# main1.net
KiCad netlist of a schematic drawn in EAGLE
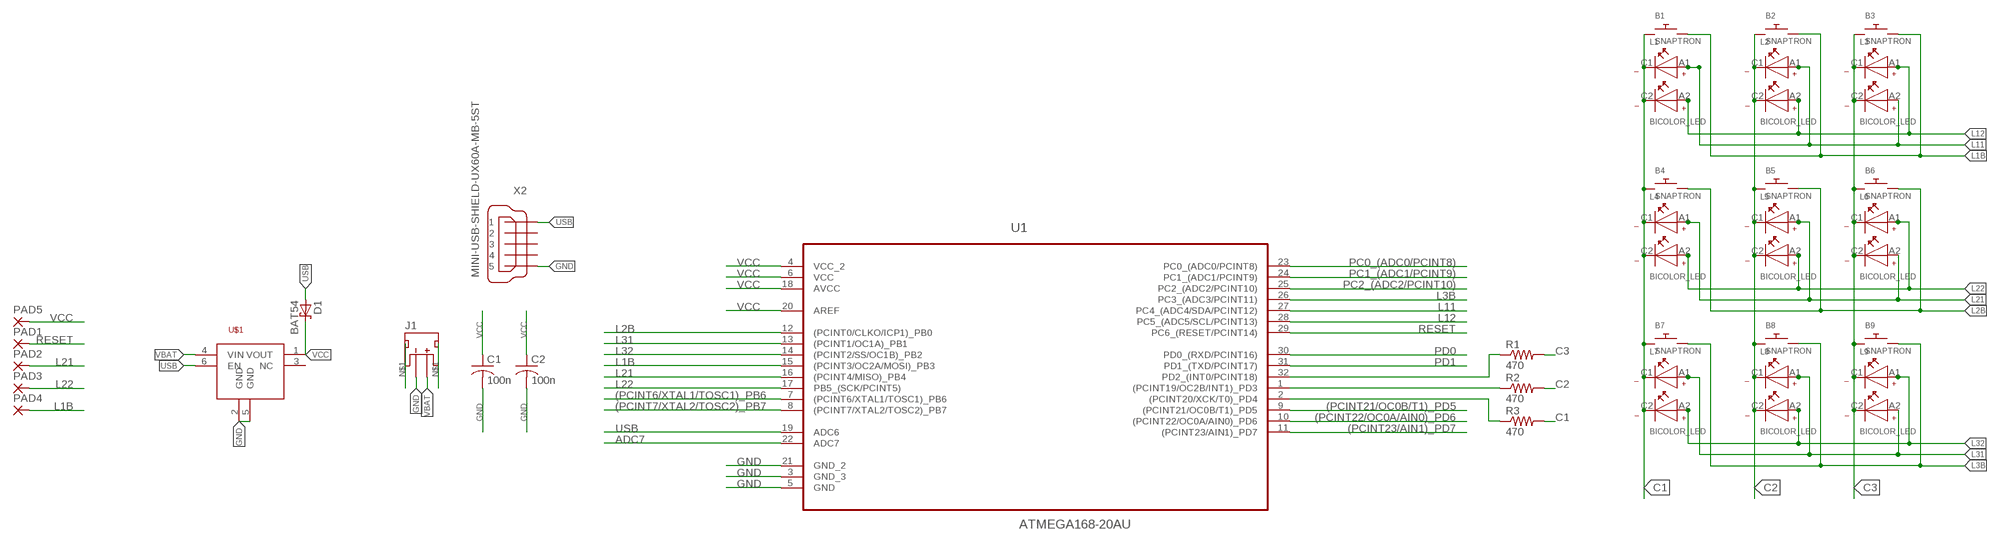
[diagram p0: schematic, sheet 1]

(export (version "E")
  (design (tool "Eeschema 10.0.6"))
  (components
    (comp (ref "B1")
      (value "SNAPTRON")
      (footprint "eagle-import:SNAPTRON-8.5")
      (libsource (lib "eagle-import") (part "SNAPTRON"))
    )
    (comp (ref "B2")
      (value "SNAPTRON")
      (footprint "eagle-import:SNAPTRON-8.5")
      (libsource (lib "eagle-import") (part "SNAPTRON"))
    )
    (comp (ref "B3")
      (value "SNAPTRON")
      (footprint "eagle-import:SNAPTRON-8.5")
      (libsource (lib "eagle-import") (part "SNAPTRON"))
    )
    (comp (ref "B4")
      (value "SNAPTRON")
      (footprint "eagle-import:SNAPTRON-8.5")
      (libsource (lib "eagle-import") (part "SNAPTRON"))
    )
    (comp (ref "B5")
      (value "SNAPTRON")
      (footprint "eagle-import:SNAPTRON-8.5")
      (libsource (lib "eagle-import") (part "SNAPTRON"))
    )
    (comp (ref "B6")
      (value "SNAPTRON")
      (footprint "eagle-import:SNAPTRON-8.5")
      (libsource (lib "eagle-import") (part "SNAPTRON"))
    )
    (comp (ref "B7")
      (value "SNAPTRON")
      (footprint "eagle-import:SNAPTRON-8.5")
      (libsource (lib "eagle-import") (part "SNAPTRON"))
    )
    (comp (ref "B8")
      (value "SNAPTRON")
      (footprint "eagle-import:SNAPTRON-8.5")
      (libsource (lib "eagle-import") (part "SNAPTRON"))
    )
    (comp (ref "B9")
      (value "SNAPTRON")
      (footprint "eagle-import:SNAPTRON-8.5")
      (libsource (lib "eagle-import") (part "SNAPTRON"))
    )
    (comp (ref "C1")
      (value "100n")
      (footprint "eagle-import:C0603")
      (libsource (lib "eagle-import") (part "C-USC0603"))
    )
    (comp (ref "C2")
      (value "100n")
      (footprint "eagle-import:C0603")
      (libsource (lib "eagle-import") (part "C-USC0603"))
    )
    (comp (ref "D1")
      (value "BAT54")
      (footprint "eagle-import:SOT23")
      (libsource (lib "eagle-import") (part "BAT54"))
    )
    (comp (ref "J1")
      (value "JST_2MM_MALE")
      (footprint "eagle-import:JST-2-SMD")
      (libsource (lib "eagle-import") (part "JST_2MM_MALE"))
    )
    (comp (ref "L1")
      (value "BICOLOR_LED")
      (footprint "eagle-import:BICOLOR_LED")
      (libsource (lib "eagle-import") (part "BICOLOR_LED"))
    )
    (comp (ref "L2")
      (value "BICOLOR_LED")
      (footprint "eagle-import:BICOLOR_LED")
      (libsource (lib "eagle-import") (part "BICOLOR_LED"))
    )
    (comp (ref "L3")
      (value "BICOLOR_LED")
      (footprint "eagle-import:BICOLOR_LED")
      (libsource (lib "eagle-import") (part "BICOLOR_LED"))
    )
    (comp (ref "L4")
      (value "BICOLOR_LED")
      (footprint "eagle-import:BICOLOR_LED")
      (libsource (lib "eagle-import") (part "BICOLOR_LED"))
    )
    (comp (ref "L5")
      (value "BICOLOR_LED")
      (footprint "eagle-import:BICOLOR_LED")
      (libsource (lib "eagle-import") (part "BICOLOR_LED"))
    )
    (comp (ref "L6")
      (value "BICOLOR_LED")
      (footprint "eagle-import:BICOLOR_LED")
      (libsource (lib "eagle-import") (part "BICOLOR_LED"))
    )
    (comp (ref "L7")
      (value "BICOLOR_LED")
      (footprint "eagle-import:BICOLOR_LED")
      (libsource (lib "eagle-import") (part "BICOLOR_LED"))
    )
    (comp (ref "L8")
      (value "BICOLOR_LED")
      (footprint "eagle-import:BICOLOR_LED")
      (libsource (lib "eagle-import") (part "BICOLOR_LED"))
    )
    (comp (ref "L9")
      (value "BICOLOR_LED")
      (footprint "eagle-import:BICOLOR_LED")
      (libsource (lib "eagle-import") (part "BICOLOR_LED"))
    )
    (comp (ref "PAD1")
      (value "SMD2")
      (footprint "eagle-import:SMD1,27-2,54")
      (libsource (lib "eagle-import") (part "SMD2"))
    )
    (comp (ref "PAD2")
      (value "SMD5")
      (footprint "eagle-import:SMD2,54-5,08")
      (libsource (lib "eagle-import") (part "SMD5"))
    )
    (comp (ref "PAD3")
      (value "SMD5")
      (footprint "eagle-import:SMD2,54-5,08")
      (libsource (lib "eagle-import") (part "SMD5"))
    )
    (comp (ref "PAD4")
      (value "SMD5")
      (footprint "eagle-import:SMD2,54-5,08")
      (libsource (lib "eagle-import") (part "SMD5"))
    )
    (comp (ref "PAD5")
      (value "SMD2")
      (footprint "eagle-import:SMD1,27-2,54")
      (libsource (lib "eagle-import") (part "SMD2"))
    )
    (comp (ref "R1")
      (value "470")
      (footprint "eagle-import:R0603")
      (libsource (lib "eagle-import") (part "R-US_R0603"))
    )
    (comp (ref "R2")
      (value "470")
      (footprint "eagle-import:R0603")
      (libsource (lib "eagle-import") (part "R-US_R0603"))
    )
    (comp (ref "R3")
      (value "470")
      (footprint "eagle-import:R0603")
      (libsource (lib "eagle-import") (part "R-US_R0603"))
    )
    (comp (ref "U$1")
      (value "MIC94090")
      (footprint "eagle-import:SC70-6L")
      (libsource (lib "eagle-import") (part "MIC94090"))
    )
    (comp (ref "U1")
      (value "ATMEGA168-20AU")
      (footprint "eagle-import:QFP80P900X900X120-32N")
      (libsource (lib "eagle-import") (part "ATMEGA168-20AU"))
    )
    (comp (ref "X2")
      (value "MINI-USB-SHIELD-UX60A-MB-5ST")
      (footprint "eagle-import:UX60A-MB-5ST")
      (libsource (lib "eagle-import") (part "MINI-USB-SHIELD-UX60A-MB-5ST"))
    )
  )
  (nets
    (net (code "1") (name "/(PCINT6{slash}XTAL1{slash}TOSC1)_PB6") (class "Default")
      (node (ref "U1") (pin "7") (pinfunction "(PCINT6/XTAL1/TOSC1)_PB6_7") (pintype "bidirectional"))
    )
    (net (code "2") (name "/(PCINT7{slash}XTAL2{slash}TOSC2)_PB7") (class "Default")
      (node (ref "U1") (pin "8") (pinfunction "(PCINT7/XTAL2/TOSC2)_PB7_8") (pintype "bidirectional"))
    )
    (net (code "3") (name "/(PCINT21{slash}OC0B{slash}T1)_PD5") (class "Default")
      (node (ref "U1") (pin "9") (pinfunction "(PCINT21/OC0B/T1)_PD5_9") (pintype "bidirectional"))
    )
    (net (code "4") (name "/(PCINT22{slash}OC0A{slash}AIN0)_PD6") (class "Default")
      (node (ref "U1") (pin "10") (pinfunction "(PCINT22/OC0A/AIN0)_PD6_10") (pintype "bidirectional"))
    )
    (net (code "5") (name "/(PCINT23{slash}AIN1)_PD7") (class "Default")
      (node (ref "U1") (pin "11") (pinfunction "(PCINT23/AIN1)_PD7_11") (pintype "bidirectional"))
    )
    (net (code "6") (name "/ADC7") (class "Default")
      (node (ref "U1") (pin "22") (pinfunction "ADC7_22") (pintype "input"))
    )
    (net (code "7") (name "/N$1") (class "Default")
      (node (ref "J1") (pin "NC1") (pinfunction "PAD1_NC1") (pintype "bidirectional"))
      (node (ref "J1") (pin "NC2") (pinfunction "PAD2_NC2") (pintype "bidirectional"))
    )
    (net (code "8") (name "/PC0_(ADC0{slash}PCINT8)") (class "Default")
      (node (ref "U1") (pin "23") (pinfunction "PC0_(ADC0/PCINT8)_23") (pintype "bidirectional"))
    )
    (net (code "9") (name "/PC1_(ADC1{slash}PCINT9)") (class "Default")
      (node (ref "U1") (pin "24") (pinfunction "PC1_(ADC1/PCINT9)_24") (pintype "bidirectional"))
    )
    (net (code "10") (name "/PC2_(ADC2{slash}PCINT10)") (class "Default")
      (node (ref "U1") (pin "25") (pinfunction "PC2_(ADC2/PCINT10)_25") (pintype "bidirectional"))
    )
    (net (code "11") (name "/PD0") (class "Default")
      (node (ref "U1") (pin "30") (pinfunction "PD0_(RXD/PCINT16)_30") (pintype "bidirectional"))
    )
    (net (code "12") (name "/PD1") (class "Default")
      (node (ref "U1") (pin "31") (pinfunction "PD1_(TXD/PCINT17)_31") (pintype "bidirectional"))
    )
    (net (code "13") (name "/RESET") (class "Default")
      (node (ref "PAD1") (pin "1") (pinfunction "P_1") (pintype "passive"))
      (node (ref "U1") (pin "29") (pinfunction "PC6_(RESET/PCINT14)_29") (pintype "bidirectional"))
    )
    (net (code "14") (name "C1") (class "Default")
      (node (ref "B1") (pin "P$1") (pinfunction "P$1_P$1") (pintype "passive"))
      (node (ref "B4") (pin "P$1") (pinfunction "P$1_P$1") (pintype "passive"))
      (node (ref "B7") (pin "P$1") (pinfunction "P$1_P$1") (pintype "passive"))
      (node (ref "L1") (pin "C1") (pinfunction "C1_C1") (pintype "passive"))
      (node (ref "L1") (pin "C2") (pinfunction "C2_C2") (pintype "passive"))
      (node (ref "L4") (pin "C1") (pinfunction "C1_C1") (pintype "passive"))
      (node (ref "L4") (pin "C2") (pinfunction "C2_C2") (pintype "passive"))
      (node (ref "L7") (pin "C1") (pinfunction "C1_C1") (pintype "passive"))
      (node (ref "L7") (pin "C2") (pinfunction "C2_C2") (pintype "passive"))
      (node (ref "R3") (pin "2") (pinfunction "2_2") (pintype "passive"))
    )
    (net (code "15") (name "C2") (class "Default")
      (node (ref "B2") (pin "P$1") (pinfunction "P$1_P$1") (pintype "passive"))
      (node (ref "B5") (pin "P$1") (pinfunction "P$1_P$1") (pintype "passive"))
      (node (ref "B8") (pin "P$1") (pinfunction "P$1_P$1") (pintype "passive"))
      (node (ref "L2") (pin "C1") (pinfunction "C1_C1") (pintype "passive"))
      (node (ref "L2") (pin "C2") (pinfunction "C2_C2") (pintype "passive"))
      (node (ref "L5") (pin "C1") (pinfunction "C1_C1") (pintype "passive"))
      (node (ref "L5") (pin "C2") (pinfunction "C2_C2") (pintype "passive"))
      (node (ref "L8") (pin "C1") (pinfunction "C1_C1") (pintype "passive"))
      (node (ref "L8") (pin "C2") (pinfunction "C2_C2") (pintype "passive"))
      (node (ref "R2") (pin "2") (pinfunction "2_2") (pintype "passive"))
    )
    (net (code "16") (name "C3") (class "Default")
      (node (ref "B3") (pin "P$1") (pinfunction "P$1_P$1") (pintype "passive"))
      (node (ref "B6") (pin "P$1") (pinfunction "P$1_P$1") (pintype "passive"))
      (node (ref "B9") (pin "P$1") (pinfunction "P$1_P$1") (pintype "passive"))
      (node (ref "L3") (pin "C1") (pinfunction "C1_C1") (pintype "passive"))
      (node (ref "L3") (pin "C2") (pinfunction "C2_C2") (pintype "passive"))
      (node (ref "L6") (pin "C1") (pinfunction "C1_C1") (pintype "passive"))
      (node (ref "L6") (pin "C2") (pinfunction "C2_C2") (pintype "passive"))
      (node (ref "L9") (pin "C1") (pinfunction "C1_C1") (pintype "passive"))
      (node (ref "L9") (pin "C2") (pinfunction "C2_C2") (pintype "passive"))
      (node (ref "R1") (pin "2") (pinfunction "2_2") (pintype "passive"))
    )
    (net (code "17") (name "GND") (class "Default")
      (node (ref "C1") (pin "2") (pinfunction "2_2") (pintype "passive"))
      (node (ref "C2") (pin "2") (pinfunction "2_2") (pintype "passive"))
      (node (ref "J1") (pin "1") (pinfunction "-_1") (pintype "bidirectional"))
      (node (ref "U$1") (pin "2") (pinfunction "GND_2") (pintype "bidirectional"))
      (node (ref "U$1") (pin "5") (pinfunction "GND_5") (pintype "bidirectional"))
      (node (ref "U1") (pin "21") (pinfunction "GND_2_21") (pintype "passive"))
      (node (ref "U1") (pin "3") (pinfunction "GND_3_3") (pintype "passive"))
      (node (ref "U1") (pin "5") (pinfunction "GND_5") (pintype "passive"))
      (node (ref "X2") (pin "5") (pinfunction "5_5") (pintype "input"))
    )
    (net (code "18") (name "L1B") (class "Default")
      (node (ref "B1") (pin "P$2") (pinfunction "P$2_P$2") (pintype "passive"))
      (node (ref "B2") (pin "P$2") (pinfunction "P$2_P$2") (pintype "passive"))
      (node (ref "B3") (pin "P$2") (pinfunction "P$2_P$2") (pintype "passive"))
      (node (ref "PAD4") (pin "1") (pinfunction "P_1") (pintype "passive"))
      (node (ref "U1") (pin "15") (pinfunction "(PCINT3/OC2A/MOSI)_PB3_15") (pintype "bidirectional"))
    )
    (net (code "19") (name "L2B") (class "Default")
      (node (ref "B4") (pin "P$2") (pinfunction "P$2_P$2") (pintype "passive"))
      (node (ref "B5") (pin "P$2") (pinfunction "P$2_P$2") (pintype "passive"))
      (node (ref "B6") (pin "P$2") (pinfunction "P$2_P$2") (pintype "passive"))
      (node (ref "U1") (pin "12") (pinfunction "(PCINT0/CLKO/ICP1)_PB0_12") (pintype "bidirectional"))
    )
    (net (code "20") (name "L3B") (class "Default")
      (node (ref "B7") (pin "P$2") (pinfunction "P$2_P$2") (pintype "passive"))
      (node (ref "B8") (pin "P$2") (pinfunction "P$2_P$2") (pintype "passive"))
      (node (ref "B9") (pin "P$2") (pinfunction "P$2_P$2") (pintype "passive"))
      (node (ref "U1") (pin "26") (pinfunction "PC3_(ADC3/PCINT11)_26") (pintype "bidirectional"))
    )
    (net (code "21") (name "L11") (class "Default")
      (node (ref "L1") (pin "A1") (pinfunction "A1_A1") (pintype "passive"))
      (node (ref "L2") (pin "A1") (pinfunction "A1_A1") (pintype "passive"))
      (node (ref "L3") (pin "A2") (pinfunction "A2_A2") (pintype "passive"))
      (node (ref "U1") (pin "27") (pinfunction "PC4_(ADC4/SDA/PCINT12)_27") (pintype "bidirectional"))
    )
    (net (code "22") (name "L12") (class "Default")
      (node (ref "L1") (pin "A2") (pinfunction "A2_A2") (pintype "passive"))
      (node (ref "L2") (pin "A2") (pinfunction "A2_A2") (pintype "passive"))
      (node (ref "L3") (pin "A1") (pinfunction "A1_A1") (pintype "passive"))
      (node (ref "U1") (pin "28") (pinfunction "PC5_(ADC5/SCL/PCINT13)_28") (pintype "bidirectional"))
    )
    (net (code "23") (name "L21") (class "Default")
      (node (ref "L4") (pin "A1") (pinfunction "A1_A1") (pintype "passive"))
      (node (ref "L5") (pin "A1") (pinfunction "A1_A1") (pintype "passive"))
      (node (ref "L6") (pin "A2") (pinfunction "A2_A2") (pintype "passive"))
      (node (ref "PAD2") (pin "1") (pinfunction "P_1") (pintype "passive"))
      (node (ref "U1") (pin "16") (pinfunction "(PCINT4/MISO)_PB4_16") (pintype "bidirectional"))
    )
    (net (code "24") (name "L22") (class "Default")
      (node (ref "L4") (pin "A2") (pinfunction "A2_A2") (pintype "passive"))
      (node (ref "L5") (pin "A2") (pinfunction "A2_A2") (pintype "passive"))
      (node (ref "L6") (pin "A1") (pinfunction "A1_A1") (pintype "passive"))
      (node (ref "PAD3") (pin "1") (pinfunction "P_1") (pintype "passive"))
      (node (ref "U1") (pin "17") (pinfunction "PB5_(SCK/PCINT5)_17") (pintype "bidirectional"))
    )
    (net (code "25") (name "L31") (class "Default")
      (node (ref "L7") (pin "A1") (pinfunction "A1_A1") (pintype "passive"))
      (node (ref "L8") (pin "A1") (pinfunction "A1_A1") (pintype "passive"))
      (node (ref "L9") (pin "A2") (pinfunction "A2_A2") (pintype "passive"))
      (node (ref "U1") (pin "13") (pinfunction "(PCINT1/OC1A)_PB1_13") (pintype "bidirectional"))
    )
    (net (code "26") (name "L32") (class "Default")
      (node (ref "L7") (pin "A2") (pinfunction "A2_A2") (pintype "passive"))
      (node (ref "L8") (pin "A2") (pinfunction "A2_A2") (pintype "passive"))
      (node (ref "L9") (pin "A1") (pinfunction "A1_A1") (pintype "passive"))
      (node (ref "U1") (pin "14") (pinfunction "(PCINT2/SS/OC1B)_PB2_14") (pintype "bidirectional"))
    )
    (net (code "27") (name "Net-(U1-(PCINT19{slash}OC2B{slash}INT1)_PD3)") (class "Default")
      (node (ref "R2") (pin "1") (pinfunction "1_1") (pintype "passive"))
      (node (ref "U1") (pin "1") (pinfunction "(PCINT19/OC2B/INT1)_PD3_1") (pintype "bidirectional"))
    )
    (net (code "28") (name "Net-(U1-(PCINT20{slash}XCK{slash}T0)_PD4)") (class "Default")
      (node (ref "R3") (pin "1") (pinfunction "1_1") (pintype "passive"))
      (node (ref "U1") (pin "2") (pinfunction "(PCINT20/XCK/T0)_PD4_2") (pintype "bidirectional"))
    )
    (net (code "29") (name "Net-(U1-PD2_(INT0{slash}PCINT18))") (class "Default")
      (node (ref "R1") (pin "1") (pinfunction "1_1") (pintype "passive"))
      (node (ref "U1") (pin "32") (pinfunction "PD2_(INT0/PCINT18)_32") (pintype "bidirectional"))
    )
    (net (code "30") (name "USB") (class "Default")
      (node (ref "D1") (pin "1") (pinfunction "A_1") (pintype "passive"))
      (node (ref "U$1") (pin "6") (pinfunction "EN_6") (pintype "bidirectional"))
      (node (ref "U1") (pin "19") (pinfunction "ADC6_19") (pintype "input"))
      (node (ref "X2") (pin "1") (pinfunction "1_1") (pintype "input"))
    )
    (net (code "31") (name "VBAT") (class "Default")
      (node (ref "J1") (pin "2") (pinfunction "+_2") (pintype "bidirectional"))
      (node (ref "U$1") (pin "4") (pinfunction "VIN_4") (pintype "bidirectional"))
    )
    (net (code "32") (name "VCC") (class "Default")
      (node (ref "C1") (pin "1") (pinfunction "1_1") (pintype "passive"))
      (node (ref "C2") (pin "1") (pinfunction "1_1") (pintype "passive"))
      (node (ref "D1") (pin "3") (pinfunction "C_3") (pintype "passive"))
      (node (ref "PAD5") (pin "1") (pinfunction "P_1") (pintype "passive"))
      (node (ref "U$1") (pin "1") (pinfunction "VOUT_1") (pintype "bidirectional"))
      (node (ref "U1") (pin "18") (pinfunction "AVCC_18") (pintype "power_in"))
      (node (ref "U1") (pin "20") (pinfunction "AREF_20") (pintype "input"))
      (node (ref "U1") (pin "4") (pinfunction "VCC_2_4") (pintype "power_in"))
      (node (ref "U1") (pin "6") (pinfunction "VCC_6") (pintype "power_in"))
    )
    (net (code "33") (name "unconnected-(U$1-NC-Pad3)") (class "Default")
      (node (ref "U$1") (pin "3") (pinfunction "NC_3") (pintype "bidirectional"))
    )
    (net (code "34") (name "unconnected-(X2-Pad2)") (class "Default")
      (node (ref "X2") (pin "2") (pinfunction "2_2") (pintype "input"))
    )
    (net (code "35") (name "unconnected-(X2-Pad3)") (class "Default")
      (node (ref "X2") (pin "3") (pinfunction "3_3") (pintype "input"))
    )
    (net (code "36") (name "unconnected-(X2-Pad4)") (class "Default")
      (node (ref "X2") (pin "4") (pinfunction "4_4") (pintype "input"))
    )
  )
)
